# telematics_board_v2.net
KiCad netlist of a schematic drawn in EAGLE
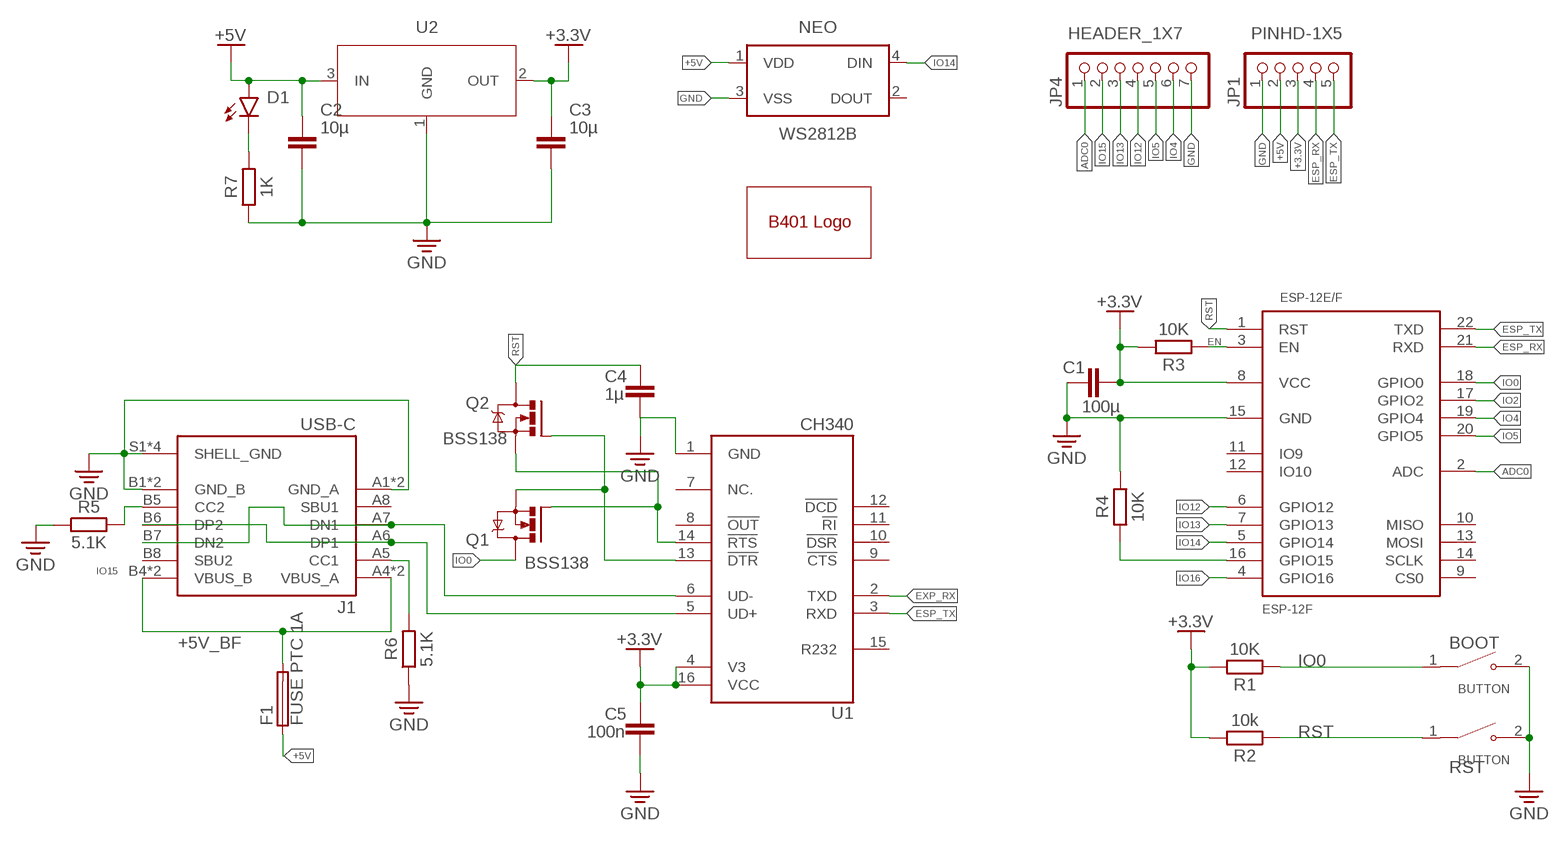
[diagram p0: schematic, sheet 1]

(export (version "E")
  (design (tool "Eeschema 10.0.6"))
  (components
    (comp (ref "BOOT")
      (value "BUTTON")
      (footprint "eagle-import:SWITCH-2P")
      (fields (field (name "MANUFACTURER") "CUI Devices"))
      (libsource (lib "eagle-import") (part "BUTTON"))
    )
    (comp (ref "C1")
      (value "100µ")
      (footprint "eagle-import:CAPM6032X280")
      (libsource (lib "eagle-import") (part "CTANTALUM-2412(6032-METRIC)_"))
    )
    (comp (ref "C2")
      (value "10µ")
      (footprint "eagle-import:CAPC2012X110")
      (libsource (lib "eagle-import") (part "CCHIP-0805(2012-METRIC)_"))
    )
    (comp (ref "C3")
      (value "10µ")
      (footprint "eagle-import:CAPC2012X110")
      (libsource (lib "eagle-import") (part "CCHIP-0805(2012-METRIC)_"))
    )
    (comp (ref "C4")
      (value "1µ")
      (footprint "eagle-import:CAPC2012X110")
      (libsource (lib "eagle-import") (part "CCHIP-0805(2012-METRIC)_"))
    )
    (comp (ref "C5")
      (value "100n")
      (footprint "eagle-import:CAPC2012X110")
      (libsource (lib "eagle-import") (part "CCHIP-0805(2012-METRIC)_"))
    )
    (comp (ref "D1")
      (value "LED_RED")
      (footprint "eagle-import:LEDC2012X110N_FLAT-R")
      (libsource (lib "eagle-import") (part "CHIP-FLAT-R_0805"))
    )
    (comp (ref "ESP-12E/F")
      (value "ESP-12F")
      (footprint "eagle-import:ESP-12F")
      (libsource (lib "eagle-import") (part "ESP-12F"))
    )
    (comp (ref "F1")
      (value "FUSE PTC 1A")
      (footprint "eagle-import:FUSC3215X82N")
      (libsource (lib "eagle-import") (part "FUSECHIP-1206(3216-METRIC)_"))
    )
    (comp (ref "J1")
      (value "USB-C")
      (footprint "eagle-import:USB-C-16P")
      (fields (field (name "MF") "Valcon") (field (name "MP") "CSP-USC16-TR"))
      (libsource (lib "eagle-import") (part "USB-C"))
    )
    (comp (ref "JP1")
      (value "PINHD-1X5")
      (footprint "eagle-import:1X05")
      (fields (field (name "MANUFACTURER") "Generic"))
      (libsource (lib "eagle-import") (part "HEADER_1X5"))
    )
    (comp (ref "JP4")
      (value "HEADER_1X7")
      (footprint "eagle-import:1X07")
      (fields (field (name "MANUFACTURER") "Generic"))
      (libsource (lib "eagle-import") (part "HEADER_1X7"))
    )
    (comp (ref "NEO")
      (value "WS2812B")
      (footprint "eagle-import:WS2812B")
      (fields (field (name "MANUFACTURER") "Worldsemi"))
      (libsource (lib "eagle-import") (part "WS2812B"))
    )
    (comp (ref "Q1")
      (value "BSS138")
      (footprint "eagle-import:SOT23")
      (libsource (lib "eagle-import") (part "NMOSFETSOT23-GSD"))
    )
    (comp (ref "Q2")
      (value "BSS138")
      (footprint "eagle-import:SOT23")
      (libsource (lib "eagle-import") (part "NMOSFETSOT23-GSD"))
    )
    (comp (ref "R1")
      (value "10K")
      (footprint "eagle-import:RESC2012X65")
      (libsource (lib "eagle-import") (part "RCHIP-0805(2012-METRIC)_"))
    )
    (comp (ref "R2")
      (value "10k")
      (footprint "eagle-import:RESC2012X65")
      (libsource (lib "eagle-import") (part "RCHIP-0805(2012-METRIC)_"))
    )
    (comp (ref "R3")
      (value "10K")
      (footprint "eagle-import:RESC2012X65")
      (libsource (lib "eagle-import") (part "RCHIP-0805(2012-METRIC)_"))
    )
    (comp (ref "R4")
      (value "10K")
      (footprint "eagle-import:RESC2012X65")
      (libsource (lib "eagle-import") (part "RCHIP-0805(2012-METRIC)_"))
    )
    (comp (ref "R5")
      (value "5.1K")
      (footprint "eagle-import:RESC2012X65")
      (libsource (lib "eagle-import") (part "RCHIP-0805(2012-METRIC)_"))
    )
    (comp (ref "R6")
      (value "5.1K")
      (footprint "eagle-import:RESC2012X65")
      (libsource (lib "eagle-import") (part "RCHIP-0805(2012-METRIC)_"))
    )
    (comp (ref "R7")
      (value "1K")
      (footprint "eagle-import:RESC2012X65")
      (libsource (lib "eagle-import") (part "RCHIP-0805(2012-METRIC)_"))
    )
    (comp (ref "RST")
      (value "BUTTON")
      (footprint "eagle-import:SWITCH-2P")
      (fields (field (name "MANUFACTURER") "CUI Devices"))
      (libsource (lib "eagle-import") (part "BUTTON"))
    )
    (comp (ref "U$1")
      (value "LOGO_B401LARGE")
      (footprint "eagle-import:B401_LARGE")
      (libsource (lib "eagle-import") (part "LOGO_B401LARGE"))
    )
    (comp (ref "U1")
      (value "CH340")
      (footprint "eagle-import:SOIC127P600X180-16N")
      (fields (field (name "MF") "WCH") (field (name "MP") "CH340C"))
      (libsource (lib "eagle-import") (part "CH340"))
    )
    (comp (ref "U2")
      (value "NCP1117ST33T3G")
      (footprint "eagle-import:SOT230P700X170-4")
      (fields (field (name "MANUFACTURER") "ON Semiconductor"))
      (libsource (lib "eagle-import") (part "NCP1117ST33T3GSOT-223"))
    )
  )
  (nets
    (net (code "1") (name "+3.3V") (class "Default")
      (node (ref "C1") (pin "2") (pinfunction "2_2") (pintype "passive"))
      (node (ref "C3") (pin "1") (pinfunction "1_1") (pintype "passive"))
      (node (ref "C5") (pin "1") (pinfunction "1_1") (pintype "passive"))
      (node (ref "ESP-12E/F") (pin "8") (pinfunction "VCC_8") (pintype "bidirectional"))
      (node (ref "JP1") (pin "3") (pinfunction "3_3") (pintype "passive"))
      (node (ref "R1") (pin "2") (pinfunction "2_2") (pintype "passive"))
      (node (ref "R2") (pin "2") (pinfunction "2_2") (pintype "passive"))
      (node (ref "R3") (pin "2") (pinfunction "2_2") (pintype "passive"))
      (node (ref "U1") (pin "16") (pinfunction "VCC_16") (pintype "power_in"))
      (node (ref "U1") (pin "4") (pinfunction "V3_4") (pintype "power_in"))
      (node (ref "U2") (pin "2") (pinfunction "OUT_2") (pintype "output"))
    )
    (net (code "2") (name "+5V") (class "Default")
      (node (ref "C2") (pin "1") (pinfunction "1_1") (pintype "passive"))
      (node (ref "D1") (pin "A") (pinfunction "A_A") (pintype "passive"))
      (node (ref "F1") (pin "1") (pinfunction "1_1") (pintype "passive"))
      (node (ref "JP1") (pin "2") (pinfunction "2_2") (pintype "passive"))
      (node (ref "NEO") (pin "1") (pinfunction "VDD_1") (pintype "power_in"))
      (node (ref "U2") (pin "3") (pinfunction "IN_3") (pintype "input"))
    )
    (net (code "3") (name "/+5V_BF") (class "Default")
      (node (ref "F1") (pin "2") (pinfunction "2_2") (pintype "passive"))
      (node (ref "J1") (pin "A4") (pinfunction "VBUS_A_A4") (pintype "power_in"))
      (node (ref "J1") (pin "A9") (pinfunction "VBUS_A_A9") (pintype "power_in"))
      (node (ref "J1") (pin "B4") (pinfunction "VBUS_B_B4") (pintype "power_in"))
      (node (ref "J1") (pin "B9") (pinfunction "VBUS_B_B9") (pintype "power_in"))
    )
    (net (code "4") (name "/EN") (class "Default")
      (node (ref "ESP-12E/F") (pin "3") (pinfunction "EN_3") (pintype "bidirectional"))
      (node (ref "R3") (pin "1") (pinfunction "1_1") (pintype "passive"))
    )
    (net (code "5") (name "ADC0") (class "Default")
      (node (ref "ESP-12E/F") (pin "2") (pinfunction "ADC_2") (pintype "bidirectional"))
      (node (ref "JP4") (pin "1") (pinfunction "1_1") (pintype "passive"))
    )
    (net (code "6") (name "ESP_RX") (class "Default")
      (node (ref "ESP-12E/F") (pin "21") (pinfunction "RXD_21") (pintype "bidirectional"))
      (node (ref "JP1") (pin "4") (pinfunction "4_4") (pintype "passive"))
    )
    (net (code "7") (name "ESP_TX") (class "Default")
      (node (ref "ESP-12E/F") (pin "22") (pinfunction "TXD_22") (pintype "bidirectional"))
      (node (ref "JP1") (pin "5") (pinfunction "5_5") (pintype "passive"))
      (node (ref "U1") (pin "3") (pinfunction "RXD_3") (pintype "input"))
    )
    (net (code "8") (name "EXP_RX") (class "Default")
      (node (ref "U1") (pin "2") (pinfunction "TXD_2") (pintype "output"))
    )
    (net (code "9") (name "GND") (class "Default")
      (node (ref "BOOT") (pin "2") (pinfunction "2_2") (pintype "passive"))
      (node (ref "C1") (pin "1") (pinfunction "1_1") (pintype "passive"))
      (node (ref "C2") (pin "2") (pinfunction "2_2") (pintype "passive"))
      (node (ref "C3") (pin "2") (pinfunction "2_2") (pintype "passive"))
      (node (ref "C4") (pin "2") (pinfunction "2_2") (pintype "passive"))
      (node (ref "C5") (pin "2") (pinfunction "2_2") (pintype "passive"))
      (node (ref "ESP-12E/F") (pin "15") (pinfunction "GND_15") (pintype "bidirectional"))
      (node (ref "J1") (pin "A1") (pinfunction "GND_A_A1") (pintype "power_in"))
      (node (ref "J1") (pin "A12") (pinfunction "GND_A_A12") (pintype "power_in"))
      (node (ref "J1") (pin "B1") (pinfunction "GND_B_B1") (pintype "power_in"))
      (node (ref "J1") (pin "B12") (pinfunction "GND_B_B12") (pintype "power_in"))
      (node (ref "J1") (pin "S1") (pinfunction "SHELL_GND_S1") (pintype "power_in"))
      (node (ref "J1") (pin "S2") (pinfunction "SHELL_GND_S2") (pintype "power_in"))
      (node (ref "J1") (pin "S3") (pinfunction "SHELL_GND_S3") (pintype "power_in"))
      (node (ref "J1") (pin "S4") (pinfunction "SHELL_GND_S4") (pintype "power_in"))
      (node (ref "JP1") (pin "1") (pinfunction "1_1") (pintype "passive"))
      (node (ref "JP4") (pin "7") (pinfunction "7_7") (pintype "passive"))
      (node (ref "NEO") (pin "3") (pinfunction "VSS_3") (pintype "power_in"))
      (node (ref "R4") (pin "2") (pinfunction "2_2") (pintype "passive"))
      (node (ref "R5") (pin "1") (pinfunction "1_1") (pintype "passive"))
      (node (ref "R6") (pin "1") (pinfunction "1_1") (pintype "passive"))
      (node (ref "R7") (pin "1") (pinfunction "1_1") (pintype "passive"))
      (node (ref "RST") (pin "2") (pinfunction "2_2") (pintype "passive"))
      (node (ref "U1") (pin "1") (pinfunction "GND_1") (pintype "power_in"))
      (node (ref "U2") (pin "1") (pinfunction "GND_1") (pintype "passive"))
    )
    (net (code "10") (name "IO0") (class "Default")
      (node (ref "BOOT") (pin "1") (pinfunction "1_1") (pintype "passive"))
      (node (ref "ESP-12E/F") (pin "18") (pinfunction "GPIO0_18") (pintype "bidirectional"))
      (node (ref "Q1") (pin "3") (pinfunction "D_3") (pintype "passive"))
      (node (ref "R1") (pin "1") (pinfunction "1_1") (pintype "passive"))
    )
    (net (code "11") (name "IO2") (class "Default")
      (node (ref "ESP-12E/F") (pin "17") (pinfunction "GPIO2_17") (pintype "bidirectional"))
    )
    (net (code "12") (name "IO4") (class "Default")
      (node (ref "ESP-12E/F") (pin "19") (pinfunction "GPIO4_19") (pintype "bidirectional"))
      (node (ref "JP4") (pin "6") (pinfunction "6_6") (pintype "passive"))
    )
    (net (code "13") (name "IO5") (class "Default")
      (node (ref "ESP-12E/F") (pin "20") (pinfunction "GPIO5_20") (pintype "bidirectional"))
      (node (ref "JP4") (pin "5") (pinfunction "5_5") (pintype "passive"))
    )
    (net (code "14") (name "IO12") (class "Default")
      (node (ref "ESP-12E/F") (pin "6") (pinfunction "GPIO12_6") (pintype "bidirectional"))
      (node (ref "JP4") (pin "4") (pinfunction "4_4") (pintype "passive"))
    )
    (net (code "15") (name "IO13") (class "Default")
      (node (ref "ESP-12E/F") (pin "7") (pinfunction "GPIO13_7") (pintype "bidirectional"))
      (node (ref "JP4") (pin "3") (pinfunction "3_3") (pintype "passive"))
    )
    (net (code "16") (name "IO14") (class "Default")
      (node (ref "ESP-12E/F") (pin "5") (pinfunction "GPIO14_5") (pintype "bidirectional"))
      (node (ref "NEO") (pin "4") (pinfunction "DIN_4") (pintype "input"))
    )
    (net (code "17") (name "IO15") (class "Default")
      (node (ref "ESP-12E/F") (pin "16") (pinfunction "GPIO15_16") (pintype "bidirectional"))
      (node (ref "JP4") (pin "2") (pinfunction "2_2") (pintype "passive"))
      (node (ref "R4") (pin "1") (pinfunction "1_1") (pintype "passive"))
    )
    (net (code "18") (name "IO16") (class "Default")
      (node (ref "ESP-12E/F") (pin "4") (pinfunction "GPIO16_4") (pintype "bidirectional"))
    )
    (net (code "19") (name "Net-(D1-PadC)") (class "Default")
      (node (ref "D1") (pin "C") (pinfunction "C_C") (pintype "passive"))
      (node (ref "R7") (pin "2") (pinfunction "2_2") (pintype "passive"))
    )
    (net (code "20") (name "Net-(J1-CC1)") (class "Default")
      (node (ref "J1") (pin "A5") (pinfunction "CC1_A5") (pintype "bidirectional"))
      (node (ref "R6") (pin "2") (pinfunction "2_2") (pintype "passive"))
    )
    (net (code "21") (name "Net-(J1-CC2)") (class "Default")
      (node (ref "J1") (pin "B5") (pinfunction "CC2_B5") (pintype "bidirectional"))
      (node (ref "R5") (pin "2") (pinfunction "2_2") (pintype "passive"))
    )
    (net (code "22") (name "Net-(J1-DN1)") (class "Default")
      (node (ref "J1") (pin "A7") (pinfunction "DN1_A7") (pintype "bidirectional"))
      (node (ref "J1") (pin "B7") (pinfunction "DN2_B7") (pintype "bidirectional"))
      (node (ref "U1") (pin "6") (pinfunction "UD-_6") (pintype "bidirectional"))
    )
    (net (code "23") (name "Net-(J1-DP1)") (class "Default")
      (node (ref "J1") (pin "A6") (pinfunction "DP1_A6") (pintype "bidirectional"))
      (node (ref "J1") (pin "B6") (pinfunction "DP2_B6") (pintype "bidirectional"))
      (node (ref "U1") (pin "5") (pinfunction "UD+_5") (pintype "bidirectional"))
    )
    (net (code "24") (name "Net-(Q1-G)") (class "Default")
      (node (ref "Q1") (pin "1") (pinfunction "G_1") (pintype "passive"))
      (node (ref "Q2") (pin "2") (pinfunction "S_2") (pintype "passive"))
      (node (ref "U1") (pin "14") (pinfunction "~{RTS}_14") (pintype "output"))
    )
    (net (code "25") (name "Net-(Q1-S)") (class "Default")
      (node (ref "Q1") (pin "2") (pinfunction "S_2") (pintype "passive"))
      (node (ref "Q2") (pin "1") (pinfunction "G_1") (pintype "passive"))
      (node (ref "U1") (pin "13") (pinfunction "~{DTR}_13") (pintype "output"))
    )
    (net (code "26") (name "RST") (class "Default")
      (node (ref "C4") (pin "1") (pinfunction "1_1") (pintype "passive"))
      (node (ref "ESP-12E/F") (pin "1") (pinfunction "RST_1") (pintype "bidirectional"))
      (node (ref "Q2") (pin "3") (pinfunction "D_3") (pintype "passive"))
      (node (ref "R2") (pin "1") (pinfunction "1_1") (pintype "passive"))
      (node (ref "RST") (pin "1") (pinfunction "1_1") (pintype "passive"))
    )
    (net (code "27") (name "unconnected-(ESP-12E/F-CS0-Pad9)") (class "Default")
      (node (ref "ESP-12E/F") (pin "9") (pinfunction "CS0_9") (pintype "bidirectional"))
    )
    (net (code "28") (name "unconnected-(ESP-12E/F-IO9-Pad11)") (class "Default")
      (node (ref "ESP-12E/F") (pin "11") (pinfunction "IO9_11") (pintype "bidirectional"))
    )
    (net (code "29") (name "unconnected-(ESP-12E/F-IO10-Pad12)") (class "Default")
      (node (ref "ESP-12E/F") (pin "12") (pinfunction "IO10_12") (pintype "bidirectional"))
    )
    (net (code "30") (name "unconnected-(ESP-12E/F-MISO-Pad10)") (class "Default")
      (node (ref "ESP-12E/F") (pin "10") (pinfunction "MISO_10") (pintype "bidirectional"))
    )
    (net (code "31") (name "unconnected-(ESP-12E/F-MOSI-Pad13)") (class "Default")
      (node (ref "ESP-12E/F") (pin "13") (pinfunction "MOSI_13") (pintype "bidirectional"))
    )
    (net (code "32") (name "unconnected-(ESP-12E/F-SCLK-Pad14)") (class "Default")
      (node (ref "ESP-12E/F") (pin "14") (pinfunction "SCLK_14") (pintype "bidirectional"))
    )
    (net (code "33") (name "unconnected-(J1-SBU1-PadA8)") (class "Default")
      (node (ref "J1") (pin "A8") (pinfunction "SBU1_A8") (pintype "bidirectional"))
    )
    (net (code "34") (name "unconnected-(J1-SBU2-PadB8)") (class "Default")
      (node (ref "J1") (pin "B8") (pinfunction "SBU2_B8") (pintype "bidirectional"))
    )
    (net (code "35") (name "unconnected-(NEO-DOUT-Pad2)") (class "Default")
      (node (ref "NEO") (pin "2") (pinfunction "DOUT_2") (pintype "output"))
    )
    (net (code "36") (name "unconnected-(U1-NC.-Pad7)") (class "Default")
      (node (ref "U1") (pin "7") (pinfunction "NC._7") (pintype "no_connect"))
    )
    (net (code "37") (name "unconnected-(U1-R232-Pad15)") (class "Default")
      (node (ref "U1") (pin "15") (pinfunction "R232_15") (pintype "input"))
    )
    (net (code "38") (name "unconnected-(U1-~{CTS}-Pad9)") (class "Default")
      (node (ref "U1") (pin "9") (pinfunction "~{CTS}_9") (pintype "input"))
    )
    (net (code "39") (name "unconnected-(U1-~{DCD}-Pad12)") (class "Default")
      (node (ref "U1") (pin "12") (pinfunction "~{DCD}_12") (pintype "input"))
    )
    (net (code "40") (name "unconnected-(U1-~{DSR}-Pad10)") (class "Default")
      (node (ref "U1") (pin "10") (pinfunction "~{DSR}_10") (pintype "input"))
    )
    (net (code "41") (name "unconnected-(U1-~{OUT}-Pad8)") (class "Default")
      (node (ref "U1") (pin "8") (pinfunction "~{OUT}_8") (pintype "output"))
    )
    (net (code "42") (name "unconnected-(U1-~{RI}-Pad11)") (class "Default")
      (node (ref "U1") (pin "11") (pinfunction "~{RI}_11") (pintype "input"))
    )
  )
)
